# soloG.net
KiCad netlist of a schematic drawn in EAGLE
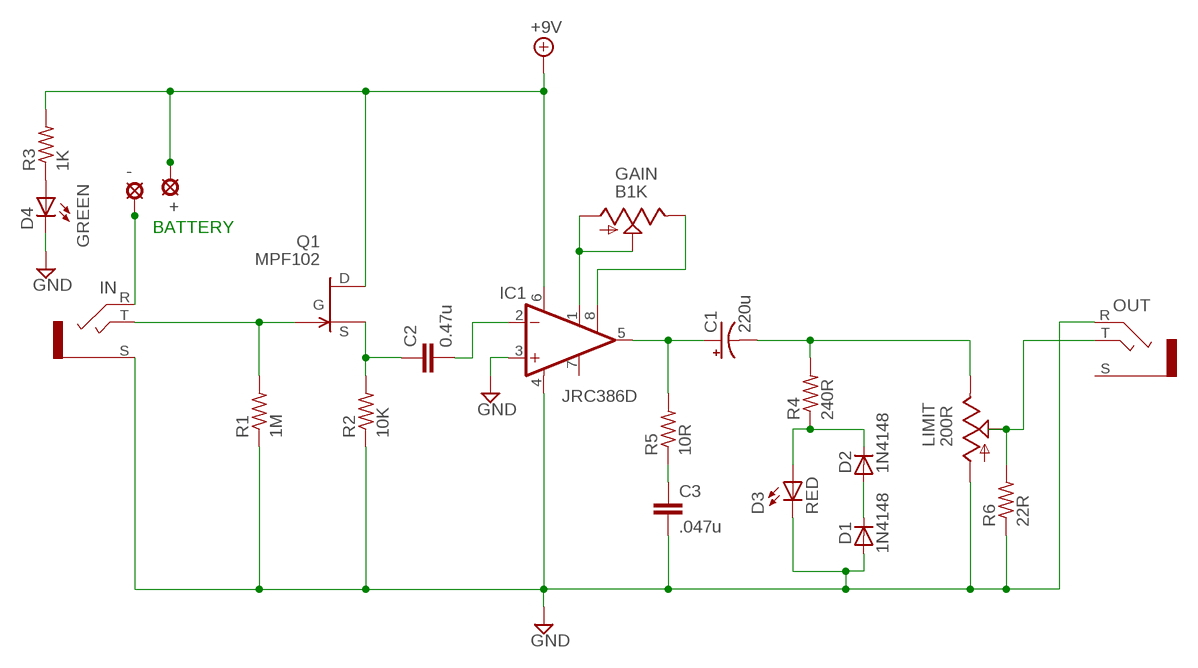
[diagram p0: schematic, sheet 1]

(export (version "E")
  (design (tool "Eeschema 10.0.6"))
  (components
    (comp (ref "+")
      (value "SOLPAD")
      (footprint "eagle-import:SOLPAD")
      (libsource (lib "eagle-import") (part "SOLPAD"))
    )
    (comp (ref "-")
      (value "SOLPAD")
      (footprint "eagle-import:SOLPAD")
      (libsource (lib "eagle-import") (part "SOLPAD"))
    )
    (comp (ref "C1")
      (value "220u")
      (footprint "eagle-import:E3,5-8")
      (libsource (lib "eagle-import") (part "CPOL-USE3.5-8"))
    )
    (comp (ref "C2")
      (value "0.47u")
      (footprint "eagle-import:C15B5")
      (libsource (lib "eagle-import") (part "C15/5"))
    )
    (comp (ref "C3")
      (value ".047u")
      (footprint "eagle-import:C075-040X085_OVAL")
      (libsource (lib "eagle-import") (part "C-EUGREEN-CHIKLET"))
    )
    (comp (ref "D1")
      (value "1N4148")
      (footprint "eagle-import:DO35-7")
      (libsource (lib "eagle-import") (part "1N4148DO35-7"))
    )
    (comp (ref "D2")
      (value "1N4148")
      (footprint "eagle-import:DO35-7")
      (libsource (lib "eagle-import") (part "1N4148DO35-7"))
    )
    (comp (ref "D3")
      (value "RED")
      (footprint "eagle-import:LED3MM")
      (libsource (lib "eagle-import") (part "LED3MM"))
    )
    (comp (ref "D4")
      (value "GREEN")
      (footprint "eagle-import:LED3MM")
      (libsource (lib "eagle-import") (part "LED3MM"))
    )
    (comp (ref "GAIN")
      (value "B1K")
      (footprint "eagle-import:PTD901-2015K")
      (libsource (lib "eagle-import") (part "TRIM_US-PTD901-2015K"))
    )
    (comp (ref "IC1")
      (value "JRC386D")
      (footprint "eagle-import:DIP8")
      (libsource (lib "eagle-import") (part "JRC386D"))
    )
    (comp (ref "IN")
      (value "NRJ6-STEREO-HH")
      (footprint "eagle-import:NRJ6HH")
      (libsource (lib "eagle-import") (part "NRJ6-STEREO-HH"))
    )
    (comp (ref "LIMIT")
      (value "200R")
      (footprint "eagle-import:0655-614")
      (libsource (lib "eagle-import") (part "TRIM_US-0655H"))
    )
    (comp (ref "OUT")
      (value "NRJ6-STEREO-HH")
      (footprint "eagle-import:NRJ6HH")
      (libsource (lib "eagle-import") (part "NRJ6-STEREO-HH"))
    )
    (comp (ref "Q1")
      (value "MPF102")
      (footprint "eagle-import:TO92-FET")
      (libsource (lib "eagle-import") (part "MPF102"))
    )
    (comp (ref "R1")
      (value "1M")
      (footprint "eagle-import:0207_7")
      (libsource (lib "eagle-import") (part "R-US_0207/7"))
    )
    (comp (ref "R2")
      (value "10K")
      (footprint "eagle-import:0207_7")
      (libsource (lib "eagle-import") (part "R-US_0207/7"))
    )
    (comp (ref "R3")
      (value "1K")
      (footprint "eagle-import:0207_7")
      (libsource (lib "eagle-import") (part "R-US_0207/7"))
    )
    (comp (ref "R4")
      (value "240R")
      (footprint "eagle-import:0207_7")
      (libsource (lib "eagle-import") (part "R-US_0207/7"))
    )
    (comp (ref "R5")
      (value "10R")
      (footprint "eagle-import:0207_7")
      (libsource (lib "eagle-import") (part "R-US_0207/7"))
    )
    (comp (ref "R6")
      (value "22R")
      (footprint "eagle-import:0207_7")
      (libsource (lib "eagle-import") (part "R-US_0207/7"))
    )
  )
  (nets
    (net (code "1") (name "+9V") (class "Default")
      (node (ref "+") (pin "1") (pinfunction "MP_1") (pintype "passive"))
      (node (ref "IC1") (pin "6") (pinfunction "VS_6") (pintype "power_in"))
      (node (ref "Q1") (pin "D") (pinfunction "D_D") (pintype "passive"))
      (node (ref "R3") (pin "2") (pinfunction "2_2") (pintype "passive"))
    )
    (net (code "2") (name "GND") (class "Default")
      (node (ref "C3") (pin "P$2") (pinfunction "2_P$2") (pintype "passive"))
      (node (ref "D1") (pin "A") (pinfunction "A_A") (pintype "passive"))
      (node (ref "D3") (pin "K") (pinfunction "C_K") (pintype "passive"))
      (node (ref "D4") (pin "K") (pinfunction "C_K") (pintype "passive"))
      (node (ref "IC1") (pin "3") (pinfunction "+IN_3") (pintype "input"))
      (node (ref "IC1") (pin "4") (pinfunction "GND_4") (pintype "power_in"))
      (node (ref "IN") (pin "S") (pinfunction "3_S") (pintype "passive"))
      (node (ref "LIMIT") (pin "A") (pinfunction "A_A") (pintype "passive"))
      (node (ref "OUT") (pin "R") (pinfunction "2_R") (pintype "passive"))
      (node (ref "R1") (pin "1") (pinfunction "1_1") (pintype "passive"))
      (node (ref "R2") (pin "1") (pinfunction "1_1") (pintype "passive"))
      (node (ref "R6") (pin "1") (pinfunction "1_1") (pintype "passive"))
    )
    (net (code "3") (name "Net-(--MP)") (class "Default")
      (node (ref "-") (pin "1") (pinfunction "MP_1") (pintype "passive"))
      (node (ref "IN") (pin "R") (pinfunction "2_R") (pintype "passive"))
    )
    (net (code "4") (name "Net-(C1-Pad-)") (class "Default")
      (node (ref "C1") (pin "-") (pinfunction "-_-") (pintype "passive"))
      (node (ref "LIMIT") (pin "E") (pinfunction "E_E") (pintype "passive"))
      (node (ref "R4") (pin "2") (pinfunction "2_2") (pintype "passive"))
    )
    (net (code "5") (name "Net-(C2-Pad1)") (class "Default")
      (node (ref "C2") (pin "1") (pinfunction "1_1") (pintype "passive"))
      (node (ref "Q1") (pin "S") (pinfunction "S_S") (pintype "passive"))
      (node (ref "R2") (pin "2") (pinfunction "2_2") (pintype "passive"))
    )
    (net (code "6") (name "Net-(C3-1)") (class "Default")
      (node (ref "C3") (pin "P$1") (pinfunction "1_P$1") (pintype "passive"))
      (node (ref "R5") (pin "1") (pinfunction "1_1") (pintype "passive"))
    )
    (net (code "7") (name "Net-(D1-PadC)") (class "Default")
      (node (ref "D1") (pin "C") (pinfunction "C_C") (pintype "passive"))
      (node (ref "D2") (pin "A") (pinfunction "A_A") (pintype "passive"))
    )
    (net (code "8") (name "Net-(D2-PadC)") (class "Default")
      (node (ref "D2") (pin "C") (pinfunction "C_C") (pintype "passive"))
      (node (ref "D3") (pin "A") (pinfunction "A_A") (pintype "passive"))
      (node (ref "R4") (pin "1") (pinfunction "1_1") (pintype "passive"))
    )
    (net (code "9") (name "Net-(D4-PadA)") (class "Default")
      (node (ref "D4") (pin "A") (pinfunction "A_A") (pintype "passive"))
      (node (ref "R3") (pin "1") (pinfunction "1_1") (pintype "passive"))
    )
    (net (code "10") (name "Net-(GAIN-A)") (class "Default")
      (node (ref "GAIN") (pin "1") (pinfunction "A_1") (pintype "passive"))
      (node (ref "GAIN") (pin "2") (pinfunction "S_2") (pintype "passive"))
      (node (ref "IC1") (pin "1") (pinfunction "GAIN_1") (pintype "passive"))
    )
    (net (code "11") (name "Net-(GAIN-E)") (class "Default")
      (node (ref "GAIN") (pin "3") (pinfunction "E_3") (pintype "passive"))
      (node (ref "IC1") (pin "8") (pinfunction "GAIN_8") (pintype "passive"))
    )
    (net (code "12") (name "Net-(IC1--IN)") (class "Default")
      (node (ref "C2") (pin "2") (pinfunction "2_2") (pintype "passive"))
      (node (ref "IC1") (pin "2") (pinfunction "-IN_2") (pintype "input"))
    )
    (net (code "13") (name "Net-(IC1-OUT)") (class "Default")
      (node (ref "C1") (pin "+") (pinfunction "+_+") (pintype "passive"))
      (node (ref "IC1") (pin "5") (pinfunction "OUT_5") (pintype "output"))
      (node (ref "R5") (pin "2") (pinfunction "2_2") (pintype "passive"))
    )
    (net (code "14") (name "Net-(IN-1)") (class "Default")
      (node (ref "IN") (pin "T") (pinfunction "1_T") (pintype "passive"))
      (node (ref "Q1") (pin "G") (pinfunction "G_G") (pintype "passive"))
      (node (ref "R1") (pin "2") (pinfunction "2_2") (pintype "passive"))
    )
    (net (code "15") (name "Net-(OUT-1)") (class "Default")
      (node (ref "LIMIT") (pin "S") (pinfunction "S_S") (pintype "passive"))
      (node (ref "OUT") (pin "T") (pinfunction "1_T") (pintype "passive"))
      (node (ref "R6") (pin "2") (pinfunction "2_2") (pintype "passive"))
    )
    (net (code "16") (name "unconnected-(IC1-BYPASS-Pad7)") (class "Default")
      (node (ref "IC1") (pin "7") (pinfunction "BYPASS_7") (pintype "passive"))
    )
    (net (code "17") (name "unconnected-(OUT-3-PadS)") (class "Default")
      (node (ref "OUT") (pin "S") (pinfunction "3_S") (pintype "passive"))
    )
  )
)
